# 20_MARK_HOLE.net
KiCad netlist of a schematic drawn in Altium Designer
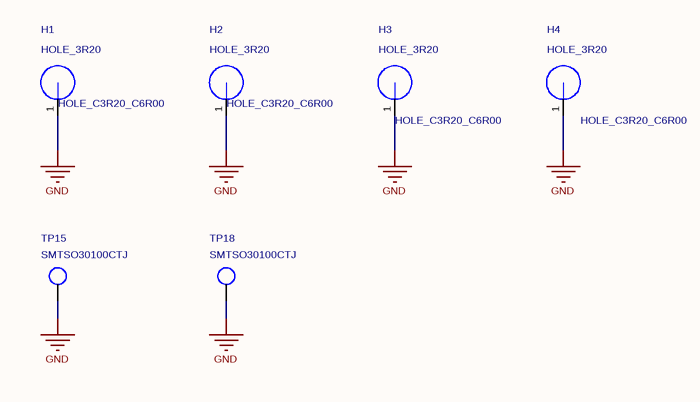
[diagram p0: 20_MARK_HOLE.SchDoc]

(export (version "E")
  (design (tool "Eeschema 10.0.6"))
  (components
    (comp (ref "H1")
      (value "HOLE_3R20")
      (footprint "HOLE_C3R20_C6R00")
      (description "直径3.2mm螺丝孔,无铜柱")
      (fields
        (field (name "PCB DECAL") "HOLE_C3R20_C6R00")
        (field (name "Comment") "HOLE")
        (field (name "CREATED_BY") "YWQ")
      )
      (libsource (lib "*") (part "HOLE"))
    )
    (comp (ref "H2")
      (value "HOLE_3R20")
      (footprint "HOLE_C3R20_C6R00")
      (description "直径3.2mm螺丝孔,无铜柱")
      (fields
        (field (name "PCB DECAL") "HOLE_C3R20_C6R00")
        (field (name "Comment") "HOLE")
        (field (name "CREATED_BY") "YWQ")
      )
      (libsource (lib "*") (part "HOLE"))
    )
    (comp (ref "H3")
      (value "HOLE_3R20")
      (footprint "HOLE_C3R20_C6R00")
      (description "直径3.2mm螺丝孔,无铜柱")
      (fields
        (field (name "PCB DECAL") "HOLE_C3R20_C6R00")
        (field (name "Comment") "HOLE")
        (field (name "CREATED_BY") "YWQ")
      )
      (libsource (lib "*") (part "HOLE"))
    )
    (comp (ref "H4")
      (value "HOLE_3R20")
      (footprint "HOLE_C3R20_C6R00")
      (description "直径3.2mm螺丝孔,无铜柱")
      (fields
        (field (name "PCB DECAL") "HOLE_C3R20_C6R00")
        (field (name "Comment") "HOLE")
        (field (name "CREATED_BY") "YWQ")
      )
      (libsource (lib "*") (part "HOLE"))
    )
    (comp (ref "TP15")
      (value "SMTSO30100CTJ")
      (footprint "PAD_10")
      (description "焊接螺母M3,高度10mm；")
      (fields (field (name "Comment") "SMTSO") (field (name "CREATED_BY") "JJJ"))
      (libsource (lib "*") (part "SMTSO"))
    )
    (comp (ref "TP18")
      (value "SMTSO30100CTJ")
      (footprint "PAD_10")
      (description "焊接螺母M3,高度10mm；")
      (fields (field (name "Comment") "SMTSO") (field (name "CREATED_BY") "JJJ"))
      (libsource (lib "*") (part "SMTSO"))
    )
  )
  (nets
    (net (code "1") (name "GND") (class "Default")
      (node (ref "H1") (pin "1") (pinfunction "1_1") (pintype "passive"))
      (node (ref "H2") (pin "1") (pinfunction "1_1") (pintype "passive"))
      (node (ref "H3") (pin "1") (pinfunction "1_1") (pintype "passive"))
      (node (ref "H4") (pin "1") (pinfunction "1_1") (pintype "passive"))
      (node (ref "TP15") (pin "1") (pinfunction "1_1") (pintype "passive"))
      (node (ref "TP18") (pin "1") (pinfunction "1_1") (pintype "passive"))
    )
  )
)
